# rgb-led-cc-driver-mk-5_0.net
KiCad netlist of a schematic drawn in EAGLE
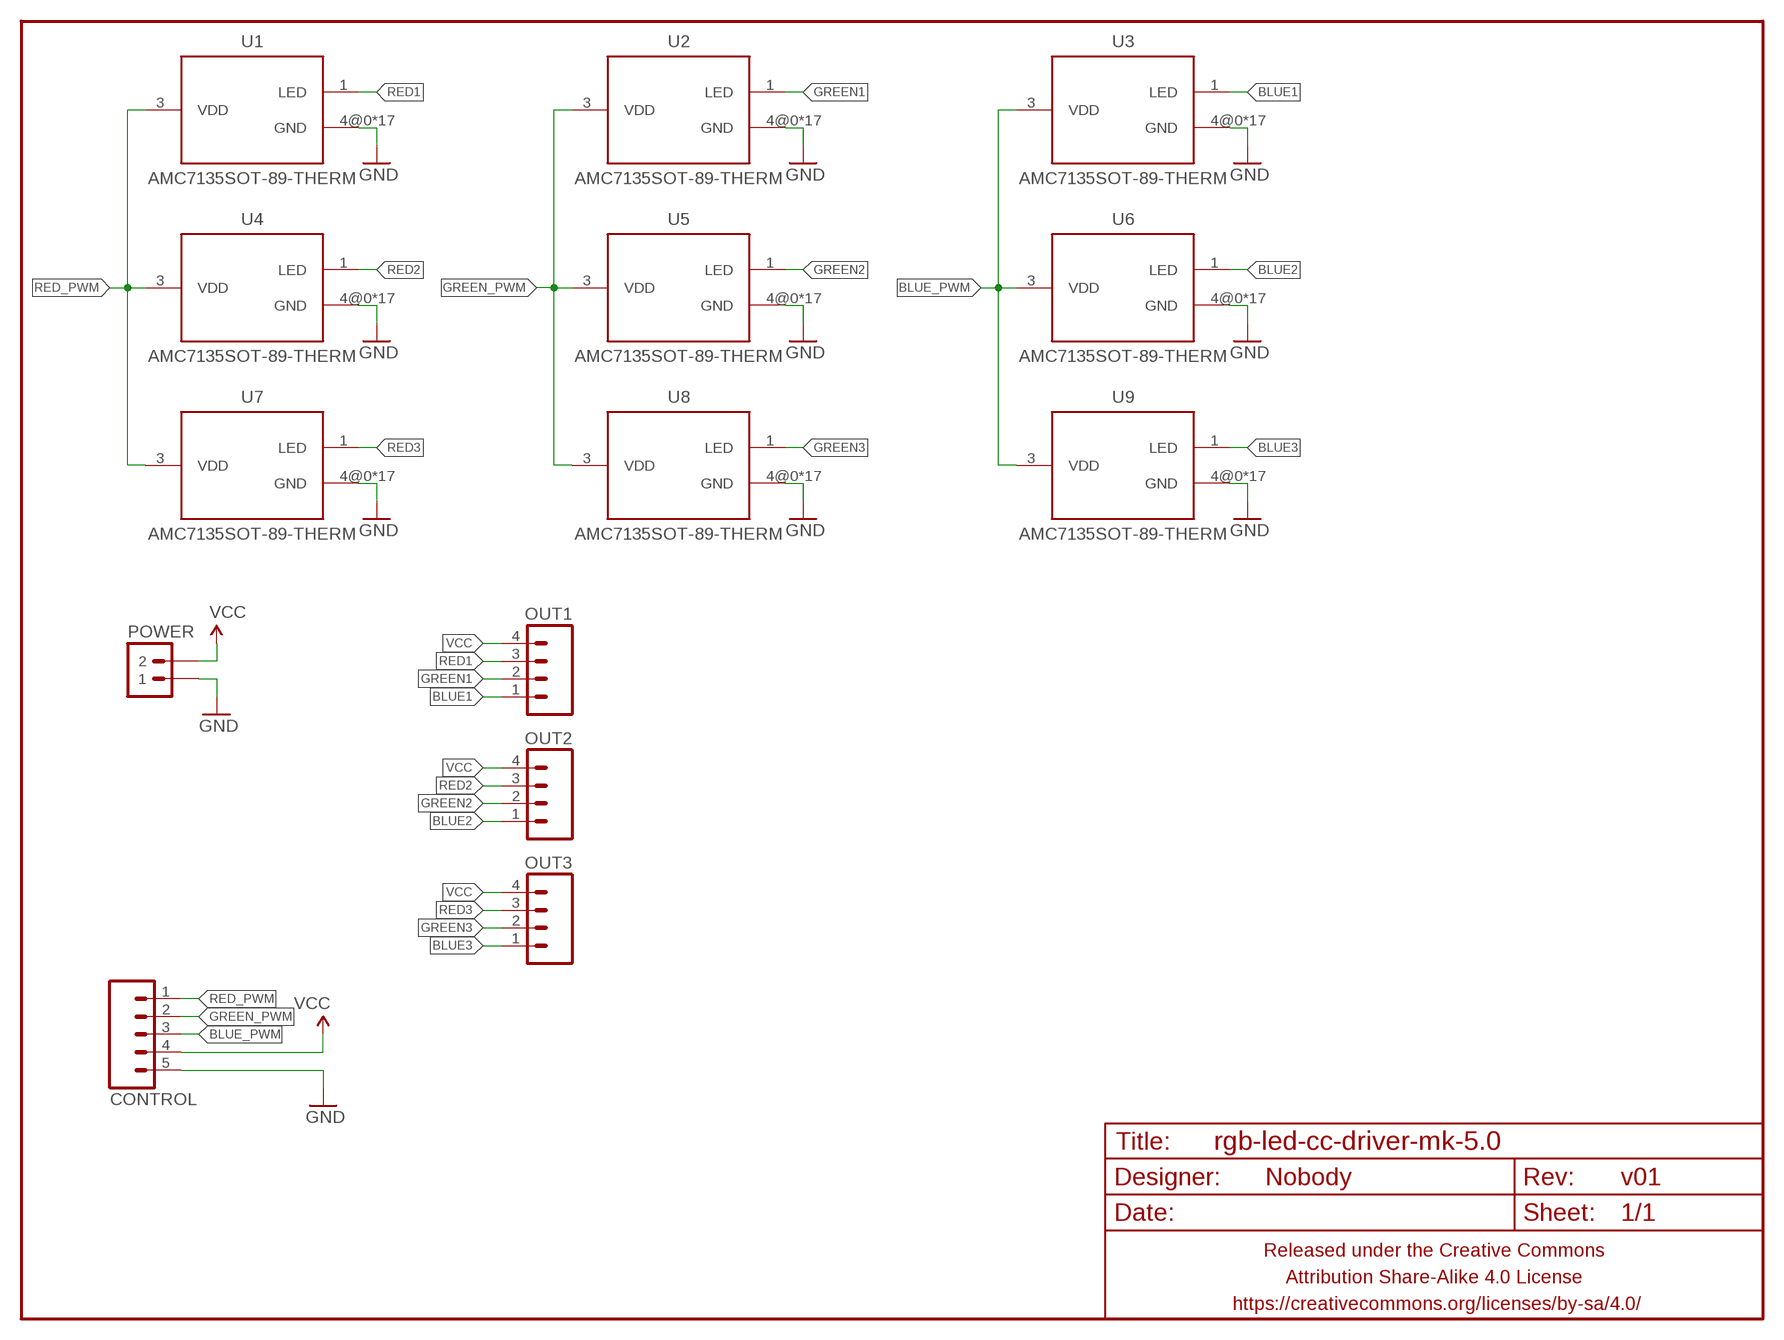
[diagram p0: schematic, sheet 1]

(export (version "E")
  (design (tool "Eeschema 10.0.6"))
  (components
    (comp (ref "CONTROL")
      (value "M05JST-PH-RA-PTH")
      (footprint "eagle-import:JST-5-PH-RA-PTH")
      (libsource (lib "eagle-import") (part "M05JST-PH-RA-PTH"))
    )
    (comp (ref "FRAME1")
      (value "FRAME-LETTERNO_PACKAGE")
      (footprint "eagle-import:DUMMY")
      (fields (field (name "DESIGNER") "Nobody"))
      (libsource (lib "eagle-import") (part "FRAME-LETTERNO_PACKAGE"))
    )
    (comp (ref "OUT1")
      (value "M04JST-PTH")
      (footprint "eagle-import:JST-4-PH-RA-PTH")
      (libsource (lib "eagle-import") (part "M04JST-PTH"))
    )
    (comp (ref "OUT2")
      (value "M04JST-PTH")
      (footprint "eagle-import:JST-4-PH-RA-PTH")
      (libsource (lib "eagle-import") (part "M04JST-PTH"))
    )
    (comp (ref "OUT3")
      (value "M04JST-PTH")
      (footprint "eagle-import:JST-4-PH-RA-PTH")
      (libsource (lib "eagle-import") (part "M04JST-PTH"))
    )
    (comp (ref "POWER")
      (value "M02PTH4")
      (footprint "eagle-import:1X02_XTRA_BIG")
      (libsource (lib "eagle-import") (part "M02PTH4"))
    )
    (comp (ref "U1")
      (value "AMC7135SOT-89-THERM")
      (footprint "eagle-import:SOT89-THERM")
      (libsource (lib "eagle-import") (part "AMC7135SOT-89-THERM"))
    )
    (comp (ref "U2")
      (value "AMC7135SOT-89-THERM")
      (footprint "eagle-import:SOT89-THERM")
      (libsource (lib "eagle-import") (part "AMC7135SOT-89-THERM"))
    )
    (comp (ref "U3")
      (value "AMC7135SOT-89-THERM")
      (footprint "eagle-import:SOT89-THERM")
      (libsource (lib "eagle-import") (part "AMC7135SOT-89-THERM"))
    )
    (comp (ref "U4")
      (value "AMC7135SOT-89-THERM")
      (footprint "eagle-import:SOT89-THERM")
      (libsource (lib "eagle-import") (part "AMC7135SOT-89-THERM"))
    )
    (comp (ref "U5")
      (value "AMC7135SOT-89-THERM")
      (footprint "eagle-import:SOT89-THERM")
      (libsource (lib "eagle-import") (part "AMC7135SOT-89-THERM"))
    )
    (comp (ref "U6")
      (value "AMC7135SOT-89-THERM")
      (footprint "eagle-import:SOT89-THERM")
      (libsource (lib "eagle-import") (part "AMC7135SOT-89-THERM"))
    )
    (comp (ref "U7")
      (value "AMC7135SOT-89-THERM")
      (footprint "eagle-import:SOT89-THERM")
      (libsource (lib "eagle-import") (part "AMC7135SOT-89-THERM"))
    )
    (comp (ref "U8")
      (value "AMC7135SOT-89-THERM")
      (footprint "eagle-import:SOT89-THERM")
      (libsource (lib "eagle-import") (part "AMC7135SOT-89-THERM"))
    )
    (comp (ref "U9")
      (value "AMC7135SOT-89-THERM")
      (footprint "eagle-import:SOT89-THERM")
      (libsource (lib "eagle-import") (part "AMC7135SOT-89-THERM"))
    )
  )
  (nets
    (net (code "1") (name "BLUE1") (class "Default")
      (node (ref "OUT1") (pin "1") (pinfunction "1_1") (pintype "passive"))
      (node (ref "U3") (pin "1") (pinfunction "LED_1") (pintype "bidirectional"))
    )
    (net (code "2") (name "BLUE2") (class "Default")
      (node (ref "OUT2") (pin "1") (pinfunction "1_1") (pintype "passive"))
      (node (ref "U6") (pin "1") (pinfunction "LED_1") (pintype "bidirectional"))
    )
    (net (code "3") (name "BLUE3") (class "Default")
      (node (ref "OUT3") (pin "1") (pinfunction "1_1") (pintype "passive"))
      (node (ref "U9") (pin "1") (pinfunction "LED_1") (pintype "bidirectional"))
    )
    (net (code "4") (name "BLUE_PWM") (class "Default")
      (node (ref "CONTROL") (pin "3") (pinfunction "3_3") (pintype "passive"))
      (node (ref "U3") (pin "3") (pinfunction "VDD_3") (pintype "bidirectional"))
      (node (ref "U6") (pin "3") (pinfunction "VDD_3") (pintype "bidirectional"))
      (node (ref "U9") (pin "3") (pinfunction "VDD_3") (pintype "bidirectional"))
    )
    (net (code "5") (name "GND") (class "Default")
      (node (ref "CONTROL") (pin "5") (pinfunction "5_5") (pintype "passive"))
      (node (ref "POWER") (pin "1") (pinfunction "1_1") (pintype "passive"))
      (node (ref "U1") (pin "4@0") (pinfunction "GND_4@0") (pintype "bidirectional"))
      (node (ref "U1") (pin "4@1") (pinfunction "GND_4@1") (pintype "bidirectional"))
      (node (ref "U1") (pin "4@10") (pinfunction "GND_4@10") (pintype "bidirectional"))
      (node (ref "U1") (pin "4@11") (pinfunction "GND_4@11") (pintype "bidirectional"))
      (node (ref "U1") (pin "4@12") (pinfunction "GND_4@12") (pintype "bidirectional"))
      (node (ref "U1") (pin "4@13") (pinfunction "GND_4@13") (pintype "bidirectional"))
      (node (ref "U1") (pin "4@14") (pinfunction "GND_4@14") (pintype "bidirectional"))
      (node (ref "U1") (pin "4@15") (pinfunction "GND_4@15") (pintype "bidirectional"))
      (node (ref "U1") (pin "4@16") (pinfunction "GND_4@16") (pintype "bidirectional"))
      (node (ref "U1") (pin "4@2") (pinfunction "GND_4@2") (pintype "bidirectional"))
      (node (ref "U1") (pin "4@3") (pinfunction "GND_4@3") (pintype "bidirectional"))
      (node (ref "U1") (pin "4@4") (pinfunction "GND_4@4") (pintype "bidirectional"))
      (node (ref "U1") (pin "4@5") (pinfunction "GND_4@5") (pintype "bidirectional"))
      (node (ref "U1") (pin "4@6") (pinfunction "GND_4@6") (pintype "bidirectional"))
      (node (ref "U1") (pin "4@7") (pinfunction "GND_4@7") (pintype "bidirectional"))
      (node (ref "U1") (pin "4@8") (pinfunction "GND_4@8") (pintype "bidirectional"))
      (node (ref "U1") (pin "4@9") (pinfunction "GND_4@9") (pintype "bidirectional"))
      (node (ref "U2") (pin "4@0") (pinfunction "GND_4@0") (pintype "bidirectional"))
      (node (ref "U2") (pin "4@1") (pinfunction "GND_4@1") (pintype "bidirectional"))
      (node (ref "U2") (pin "4@10") (pinfunction "GND_4@10") (pintype "bidirectional"))
      (node (ref "U2") (pin "4@11") (pinfunction "GND_4@11") (pintype "bidirectional"))
      (node (ref "U2") (pin "4@12") (pinfunction "GND_4@12") (pintype "bidirectional"))
      (node (ref "U2") (pin "4@13") (pinfunction "GND_4@13") (pintype "bidirectional"))
      (node (ref "U2") (pin "4@14") (pinfunction "GND_4@14") (pintype "bidirectional"))
      (node (ref "U2") (pin "4@15") (pinfunction "GND_4@15") (pintype "bidirectional"))
      (node (ref "U2") (pin "4@16") (pinfunction "GND_4@16") (pintype "bidirectional"))
      (node (ref "U2") (pin "4@2") (pinfunction "GND_4@2") (pintype "bidirectional"))
      (node (ref "U2") (pin "4@3") (pinfunction "GND_4@3") (pintype "bidirectional"))
      (node (ref "U2") (pin "4@4") (pinfunction "GND_4@4") (pintype "bidirectional"))
      (node (ref "U2") (pin "4@5") (pinfunction "GND_4@5") (pintype "bidirectional"))
      (node (ref "U2") (pin "4@6") (pinfunction "GND_4@6") (pintype "bidirectional"))
      (node (ref "U2") (pin "4@7") (pinfunction "GND_4@7") (pintype "bidirectional"))
      (node (ref "U2") (pin "4@8") (pinfunction "GND_4@8") (pintype "bidirectional"))
      (node (ref "U2") (pin "4@9") (pinfunction "GND_4@9") (pintype "bidirectional"))
      (node (ref "U3") (pin "4@0") (pinfunction "GND_4@0") (pintype "bidirectional"))
      (node (ref "U3") (pin "4@1") (pinfunction "GND_4@1") (pintype "bidirectional"))
      (node (ref "U3") (pin "4@10") (pinfunction "GND_4@10") (pintype "bidirectional"))
      (node (ref "U3") (pin "4@11") (pinfunction "GND_4@11") (pintype "bidirectional"))
      (node (ref "U3") (pin "4@12") (pinfunction "GND_4@12") (pintype "bidirectional"))
      (node (ref "U3") (pin "4@13") (pinfunction "GND_4@13") (pintype "bidirectional"))
      (node (ref "U3") (pin "4@14") (pinfunction "GND_4@14") (pintype "bidirectional"))
      (node (ref "U3") (pin "4@15") (pinfunction "GND_4@15") (pintype "bidirectional"))
      (node (ref "U3") (pin "4@16") (pinfunction "GND_4@16") (pintype "bidirectional"))
      (node (ref "U3") (pin "4@2") (pinfunction "GND_4@2") (pintype "bidirectional"))
      (node (ref "U3") (pin "4@3") (pinfunction "GND_4@3") (pintype "bidirectional"))
      (node (ref "U3") (pin "4@4") (pinfunction "GND_4@4") (pintype "bidirectional"))
      (node (ref "U3") (pin "4@5") (pinfunction "GND_4@5") (pintype "bidirectional"))
      (node (ref "U3") (pin "4@6") (pinfunction "GND_4@6") (pintype "bidirectional"))
      (node (ref "U3") (pin "4@7") (pinfunction "GND_4@7") (pintype "bidirectional"))
      (node (ref "U3") (pin "4@8") (pinfunction "GND_4@8") (pintype "bidirectional"))
      (node (ref "U3") (pin "4@9") (pinfunction "GND_4@9") (pintype "bidirectional"))
      (node (ref "U4") (pin "4@0") (pinfunction "GND_4@0") (pintype "bidirectional"))
      (node (ref "U4") (pin "4@1") (pinfunction "GND_4@1") (pintype "bidirectional"))
      (node (ref "U4") (pin "4@10") (pinfunction "GND_4@10") (pintype "bidirectional"))
      (node (ref "U4") (pin "4@11") (pinfunction "GND_4@11") (pintype "bidirectional"))
      (node (ref "U4") (pin "4@12") (pinfunction "GND_4@12") (pintype "bidirectional"))
      (node (ref "U4") (pin "4@13") (pinfunction "GND_4@13") (pintype "bidirectional"))
      (node (ref "U4") (pin "4@14") (pinfunction "GND_4@14") (pintype "bidirectional"))
      (node (ref "U4") (pin "4@15") (pinfunction "GND_4@15") (pintype "bidirectional"))
      (node (ref "U4") (pin "4@16") (pinfunction "GND_4@16") (pintype "bidirectional"))
      (node (ref "U4") (pin "4@2") (pinfunction "GND_4@2") (pintype "bidirectional"))
      (node (ref "U4") (pin "4@3") (pinfunction "GND_4@3") (pintype "bidirectional"))
      (node (ref "U4") (pin "4@4") (pinfunction "GND_4@4") (pintype "bidirectional"))
      (node (ref "U4") (pin "4@5") (pinfunction "GND_4@5") (pintype "bidirectional"))
      (node (ref "U4") (pin "4@6") (pinfunction "GND_4@6") (pintype "bidirectional"))
      (node (ref "U4") (pin "4@7") (pinfunction "GND_4@7") (pintype "bidirectional"))
      (node (ref "U4") (pin "4@8") (pinfunction "GND_4@8") (pintype "bidirectional"))
      (node (ref "U4") (pin "4@9") (pinfunction "GND_4@9") (pintype "bidirectional"))
      (node (ref "U5") (pin "4@0") (pinfunction "GND_4@0") (pintype "bidirectional"))
      (node (ref "U5") (pin "4@1") (pinfunction "GND_4@1") (pintype "bidirectional"))
      (node (ref "U5") (pin "4@10") (pinfunction "GND_4@10") (pintype "bidirectional"))
      (node (ref "U5") (pin "4@11") (pinfunction "GND_4@11") (pintype "bidirectional"))
      (node (ref "U5") (pin "4@12") (pinfunction "GND_4@12") (pintype "bidirectional"))
      (node (ref "U5") (pin "4@13") (pinfunction "GND_4@13") (pintype "bidirectional"))
      (node (ref "U5") (pin "4@14") (pinfunction "GND_4@14") (pintype "bidirectional"))
      (node (ref "U5") (pin "4@15") (pinfunction "GND_4@15") (pintype "bidirectional"))
      (node (ref "U5") (pin "4@16") (pinfunction "GND_4@16") (pintype "bidirectional"))
      (node (ref "U5") (pin "4@2") (pinfunction "GND_4@2") (pintype "bidirectional"))
      (node (ref "U5") (pin "4@3") (pinfunction "GND_4@3") (pintype "bidirectional"))
      (node (ref "U5") (pin "4@4") (pinfunction "GND_4@4") (pintype "bidirectional"))
      (node (ref "U5") (pin "4@5") (pinfunction "GND_4@5") (pintype "bidirectional"))
      (node (ref "U5") (pin "4@6") (pinfunction "GND_4@6") (pintype "bidirectional"))
      (node (ref "U5") (pin "4@7") (pinfunction "GND_4@7") (pintype "bidirectional"))
      (node (ref "U5") (pin "4@8") (pinfunction "GND_4@8") (pintype "bidirectional"))
      (node (ref "U5") (pin "4@9") (pinfunction "GND_4@9") (pintype "bidirectional"))
      (node (ref "U6") (pin "4@0") (pinfunction "GND_4@0") (pintype "bidirectional"))
      (node (ref "U6") (pin "4@1") (pinfunction "GND_4@1") (pintype "bidirectional"))
      (node (ref "U6") (pin "4@10") (pinfunction "GND_4@10") (pintype "bidirectional"))
      (node (ref "U6") (pin "4@11") (pinfunction "GND_4@11") (pintype "bidirectional"))
      (node (ref "U6") (pin "4@12") (pinfunction "GND_4@12") (pintype "bidirectional"))
      (node (ref "U6") (pin "4@13") (pinfunction "GND_4@13") (pintype "bidirectional"))
      (node (ref "U6") (pin "4@14") (pinfunction "GND_4@14") (pintype "bidirectional"))
      (node (ref "U6") (pin "4@15") (pinfunction "GND_4@15") (pintype "bidirectional"))
      (node (ref "U6") (pin "4@16") (pinfunction "GND_4@16") (pintype "bidirectional"))
      (node (ref "U6") (pin "4@2") (pinfunction "GND_4@2") (pintype "bidirectional"))
      (node (ref "U6") (pin "4@3") (pinfunction "GND_4@3") (pintype "bidirectional"))
      (node (ref "U6") (pin "4@4") (pinfunction "GND_4@4") (pintype "bidirectional"))
      (node (ref "U6") (pin "4@5") (pinfunction "GND_4@5") (pintype "bidirectional"))
      (node (ref "U6") (pin "4@6") (pinfunction "GND_4@6") (pintype "bidirectional"))
      (node (ref "U6") (pin "4@7") (pinfunction "GND_4@7") (pintype "bidirectional"))
      (node (ref "U6") (pin "4@8") (pinfunction "GND_4@8") (pintype "bidirectional"))
      (node (ref "U6") (pin "4@9") (pinfunction "GND_4@9") (pintype "bidirectional"))
      (node (ref "U7") (pin "4@0") (pinfunction "GND_4@0") (pintype "bidirectional"))
      (node (ref "U7") (pin "4@1") (pinfunction "GND_4@1") (pintype "bidirectional"))
      (node (ref "U7") (pin "4@10") (pinfunction "GND_4@10") (pintype "bidirectional"))
      (node (ref "U7") (pin "4@11") (pinfunction "GND_4@11") (pintype "bidirectional"))
      (node (ref "U7") (pin "4@12") (pinfunction "GND_4@12") (pintype "bidirectional"))
      (node (ref "U7") (pin "4@13") (pinfunction "GND_4@13") (pintype "bidirectional"))
      (node (ref "U7") (pin "4@14") (pinfunction "GND_4@14") (pintype "bidirectional"))
      (node (ref "U7") (pin "4@15") (pinfunction "GND_4@15") (pintype "bidirectional"))
      (node (ref "U7") (pin "4@16") (pinfunction "GND_4@16") (pintype "bidirectional"))
      (node (ref "U7") (pin "4@2") (pinfunction "GND_4@2") (pintype "bidirectional"))
      (node (ref "U7") (pin "4@3") (pinfunction "GND_4@3") (pintype "bidirectional"))
      (node (ref "U7") (pin "4@4") (pinfunction "GND_4@4") (pintype "bidirectional"))
      (node (ref "U7") (pin "4@5") (pinfunction "GND_4@5") (pintype "bidirectional"))
      (node (ref "U7") (pin "4@6") (pinfunction "GND_4@6") (pintype "bidirectional"))
      (node (ref "U7") (pin "4@7") (pinfunction "GND_4@7") (pintype "bidirectional"))
      (node (ref "U7") (pin "4@8") (pinfunction "GND_4@8") (pintype "bidirectional"))
      (node (ref "U7") (pin "4@9") (pinfunction "GND_4@9") (pintype "bidirectional"))
      (node (ref "U8") (pin "4@0") (pinfunction "GND_4@0") (pintype "bidirectional"))
      (node (ref "U8") (pin "4@1") (pinfunction "GND_4@1") (pintype "bidirectional"))
      (node (ref "U8") (pin "4@10") (pinfunction "GND_4@10") (pintype "bidirectional"))
      (node (ref "U8") (pin "4@11") (pinfunction "GND_4@11") (pintype "bidirectional"))
      (node (ref "U8") (pin "4@12") (pinfunction "GND_4@12") (pintype "bidirectional"))
      (node (ref "U8") (pin "4@13") (pinfunction "GND_4@13") (pintype "bidirectional"))
      (node (ref "U8") (pin "4@14") (pinfunction "GND_4@14") (pintype "bidirectional"))
      (node (ref "U8") (pin "4@15") (pinfunction "GND_4@15") (pintype "bidirectional"))
      (node (ref "U8") (pin "4@16") (pinfunction "GND_4@16") (pintype "bidirectional"))
      (node (ref "U8") (pin "4@2") (pinfunction "GND_4@2") (pintype "bidirectional"))
      (node (ref "U8") (pin "4@3") (pinfunction "GND_4@3") (pintype "bidirectional"))
      (node (ref "U8") (pin "4@4") (pinfunction "GND_4@4") (pintype "bidirectional"))
      (node (ref "U8") (pin "4@5") (pinfunction "GND_4@5") (pintype "bidirectional"))
      (node (ref "U8") (pin "4@6") (pinfunction "GND_4@6") (pintype "bidirectional"))
      (node (ref "U8") (pin "4@7") (pinfunction "GND_4@7") (pintype "bidirectional"))
      (node (ref "U8") (pin "4@8") (pinfunction "GND_4@8") (pintype "bidirectional"))
      (node (ref "U8") (pin "4@9") (pinfunction "GND_4@9") (pintype "bidirectional"))
      (node (ref "U9") (pin "4@0") (pinfunction "GND_4@0") (pintype "bidirectional"))
      (node (ref "U9") (pin "4@1") (pinfunction "GND_4@1") (pintype "bidirectional"))
      (node (ref "U9") (pin "4@10") (pinfunction "GND_4@10") (pintype "bidirectional"))
      (node (ref "U9") (pin "4@11") (pinfunction "GND_4@11") (pintype "bidirectional"))
      (node (ref "U9") (pin "4@12") (pinfunction "GND_4@12") (pintype "bidirectional"))
      (node (ref "U9") (pin "4@13") (pinfunction "GND_4@13") (pintype "bidirectional"))
      (node (ref "U9") (pin "4@14") (pinfunction "GND_4@14") (pintype "bidirectional"))
      (node (ref "U9") (pin "4@15") (pinfunction "GND_4@15") (pintype "bidirectional"))
      (node (ref "U9") (pin "4@16") (pinfunction "GND_4@16") (pintype "bidirectional"))
      (node (ref "U9") (pin "4@2") (pinfunction "GND_4@2") (pintype "bidirectional"))
      (node (ref "U9") (pin "4@3") (pinfunction "GND_4@3") (pintype "bidirectional"))
      (node (ref "U9") (pin "4@4") (pinfunction "GND_4@4") (pintype "bidirectional"))
      (node (ref "U9") (pin "4@5") (pinfunction "GND_4@5") (pintype "bidirectional"))
      (node (ref "U9") (pin "4@6") (pinfunction "GND_4@6") (pintype "bidirectional"))
      (node (ref "U9") (pin "4@7") (pinfunction "GND_4@7") (pintype "bidirectional"))
      (node (ref "U9") (pin "4@8") (pinfunction "GND_4@8") (pintype "bidirectional"))
      (node (ref "U9") (pin "4@9") (pinfunction "GND_4@9") (pintype "bidirectional"))
    )
    (net (code "6") (name "GREEN1") (class "Default")
      (node (ref "OUT1") (pin "2") (pinfunction "2_2") (pintype "passive"))
      (node (ref "U2") (pin "1") (pinfunction "LED_1") (pintype "bidirectional"))
    )
    (net (code "7") (name "GREEN2") (class "Default")
      (node (ref "OUT2") (pin "2") (pinfunction "2_2") (pintype "passive"))
      (node (ref "U5") (pin "1") (pinfunction "LED_1") (pintype "bidirectional"))
    )
    (net (code "8") (name "GREEN3") (class "Default")
      (node (ref "OUT3") (pin "2") (pinfunction "2_2") (pintype "passive"))
      (node (ref "U8") (pin "1") (pinfunction "LED_1") (pintype "bidirectional"))
    )
    (net (code "9") (name "GREEN_PWM") (class "Default")
      (node (ref "CONTROL") (pin "2") (pinfunction "2_2") (pintype "passive"))
      (node (ref "U2") (pin "3") (pinfunction "VDD_3") (pintype "bidirectional"))
      (node (ref "U5") (pin "3") (pinfunction "VDD_3") (pintype "bidirectional"))
      (node (ref "U8") (pin "3") (pinfunction "VDD_3") (pintype "bidirectional"))
    )
    (net (code "10") (name "RED1") (class "Default")
      (node (ref "OUT1") (pin "3") (pinfunction "3_3") (pintype "passive"))
      (node (ref "U1") (pin "1") (pinfunction "LED_1") (pintype "bidirectional"))
    )
    (net (code "11") (name "RED2") (class "Default")
      (node (ref "OUT2") (pin "3") (pinfunction "3_3") (pintype "passive"))
      (node (ref "U4") (pin "1") (pinfunction "LED_1") (pintype "bidirectional"))
    )
    (net (code "12") (name "RED3") (class "Default")
      (node (ref "OUT3") (pin "3") (pinfunction "3_3") (pintype "passive"))
      (node (ref "U7") (pin "1") (pinfunction "LED_1") (pintype "bidirectional"))
    )
    (net (code "13") (name "RED_PWM") (class "Default")
      (node (ref "CONTROL") (pin "1") (pinfunction "1_1") (pintype "passive"))
      (node (ref "U1") (pin "3") (pinfunction "VDD_3") (pintype "bidirectional"))
      (node (ref "U4") (pin "3") (pinfunction "VDD_3") (pintype "bidirectional"))
      (node (ref "U7") (pin "3") (pinfunction "VDD_3") (pintype "bidirectional"))
    )
    (net (code "14") (name "VCC") (class "Default")
      (node (ref "CONTROL") (pin "4") (pinfunction "4_4") (pintype "passive"))
      (node (ref "OUT1") (pin "4") (pinfunction "4_4") (pintype "passive"))
      (node (ref "OUT2") (pin "4") (pinfunction "4_4") (pintype "passive"))
      (node (ref "OUT3") (pin "4") (pinfunction "4_4") (pintype "passive"))
      (node (ref "POWER") (pin "2") (pinfunction "2_2") (pintype "passive"))
    )
  )
)
